# tally.net
KiCad netlist of a schematic drawn in EAGLE
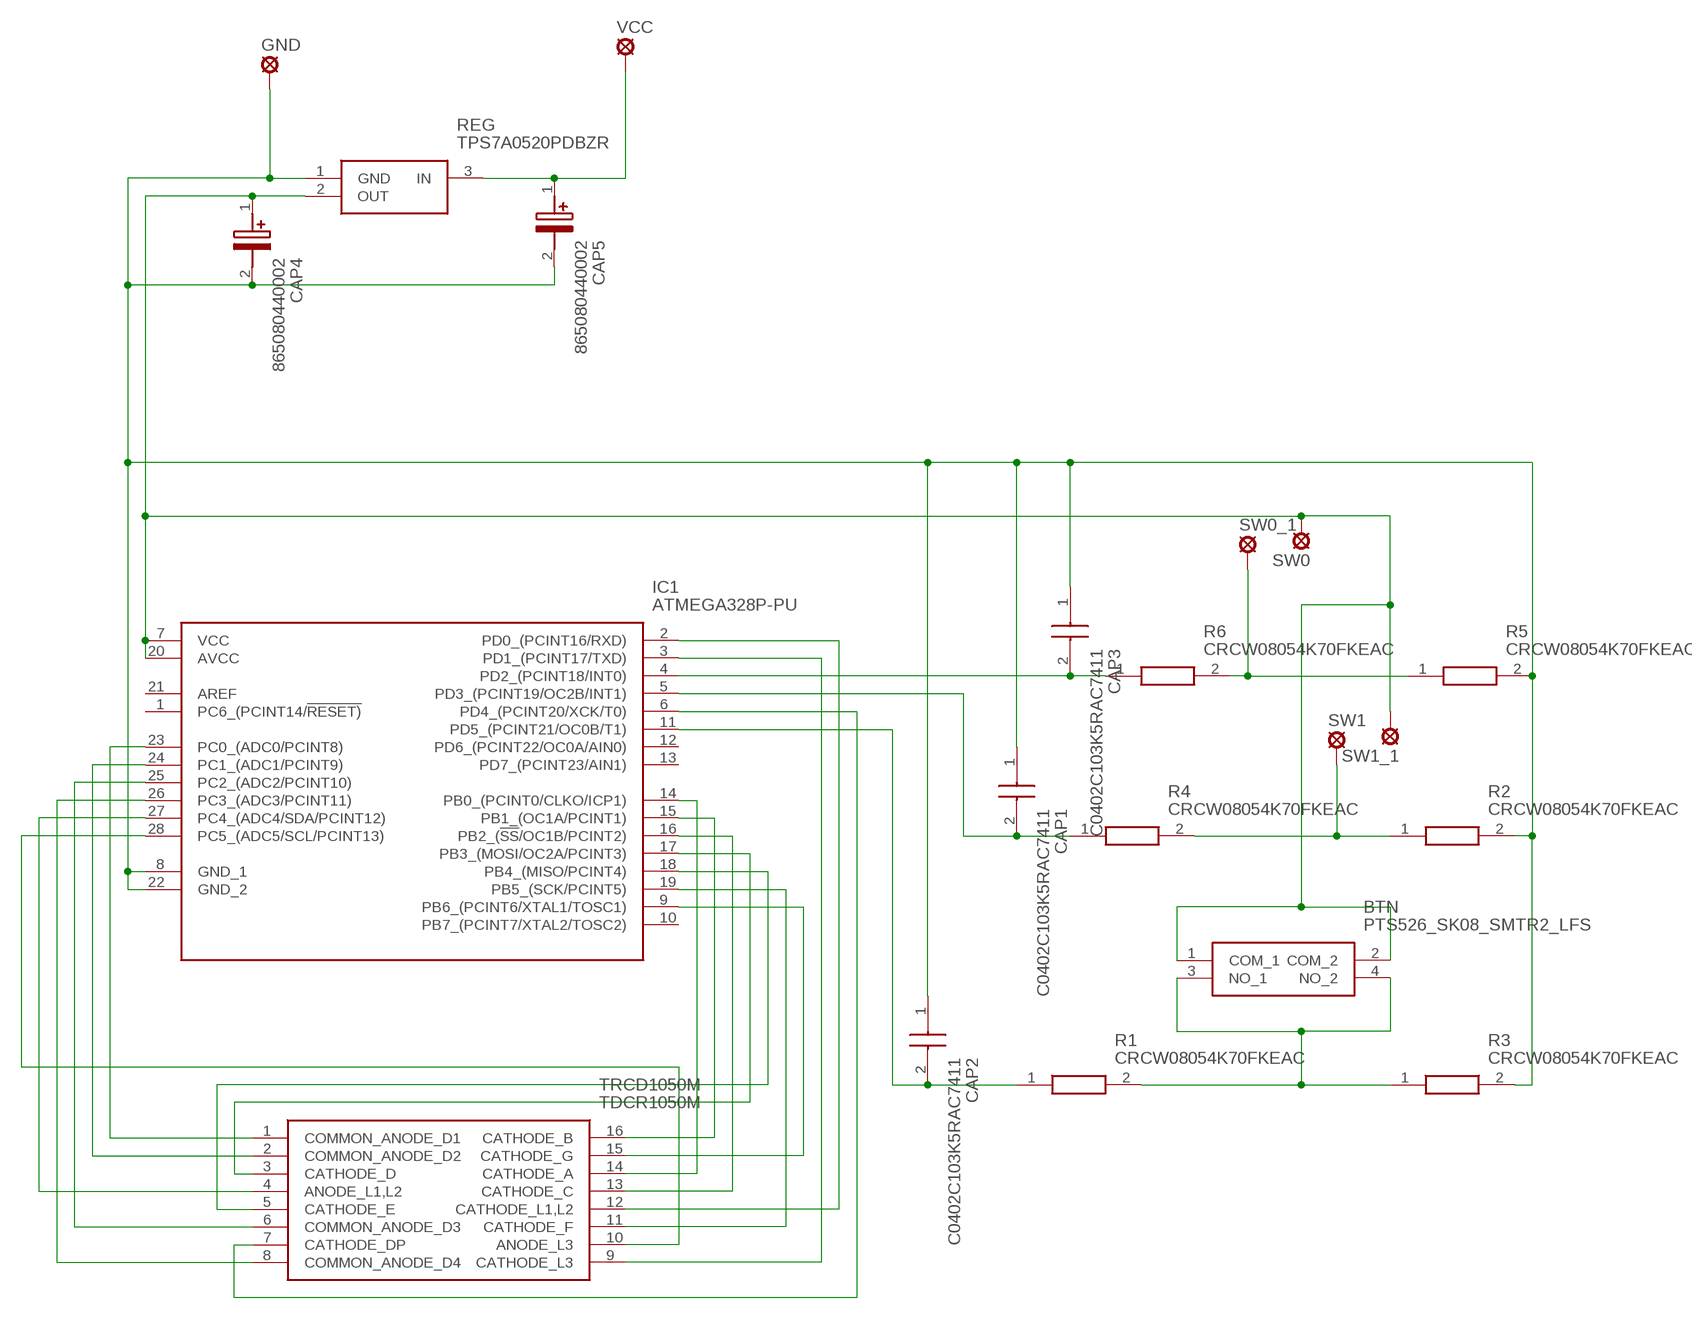
[diagram p0: schematic, sheet 1]

(export (version "E")
  (design (tool "Eeschema 10.0.6"))
  (components
    (comp (ref "BTN")
      (value "PTS526_SK08_SMTR2_LFS")
      (footprint "eagle-import:PTS526SKG15SMTR2LFS")
      (fields
        (field (name "MANUFACTURER_PART_NUMBER") "PTS526 SK08 SMTR2 LFS")
        (field (name "MOUSER_PART_NUMBER") "611-PTS526SK08SMTR2L")
      )
      (libsource (lib "eagle-import") (part "PTS526_SK08_SMTR2_LFS"))
    )
    (comp (ref "CAP1")
      (value "C0402C103K5RAC7411")
      (footprint "eagle-import:CAPC1005X55N")
      (fields (field (name "MOUSER_PART_NUMBER") "80-C0402C103K5R7411"))
      (libsource (lib "eagle-import") (part "C0402C103K5RAC7411"))
    )
    (comp (ref "CAP2")
      (value "C0402C103K5RAC7411")
      (footprint "eagle-import:CAPC1005X55N")
      (fields (field (name "MOUSER_PART_NUMBER") "80-C0402C103K5R7411"))
      (libsource (lib "eagle-import") (part "C0402C103K5RAC7411"))
    )
    (comp (ref "CAP3")
      (value "C0402C103K5RAC7411")
      (footprint "eagle-import:CAPC1005X55N")
      (fields (field (name "MOUSER_PART_NUMBER") "80-C0402C103K5R7411"))
      (libsource (lib "eagle-import") (part "C0402C103K5RAC7411"))
    )
    (comp (ref "CAP4")
      (value "865080440002")
      (footprint "eagle-import:CAPAE400X550N")
      (fields (field (name "MOUSER_PART_NUMBER") "710-865080440002"))
      (libsource (lib "eagle-import") (part "865080440002"))
    )
    (comp (ref "CAP5")
      (value "865080440002")
      (footprint "eagle-import:CAPAE400X550N")
      (fields (field (name "MOUSER_PART_NUMBER") "710-865080440002"))
      (libsource (lib "eagle-import") (part "865080440002"))
    )
    (comp (ref "GND")
      (value "LSP11")
      (footprint "eagle-import:LSP11")
      (libsource (lib "eagle-import") (part "LSP11"))
    )
    (comp (ref "IC1")
      (value "ATMEGA328P-PU")
      (footprint "eagle-import:DIP794W53P254L3467H457Q28N")
      (fields (field (name "MOUSER_PART_NUMBER") "556-ATMEGA328P-PU"))
      (libsource (lib "eagle-import") (part "ATMEGA328P-PU"))
    )
    (comp (ref "R1")
      (value "CRCW08054K70FKEAC")
      (footprint "eagle-import:RESC2012X60N")
      (fields (field (name "MOUSER_PART_NUMBER") "71-CRCW08054K70FKEAC"))
      (libsource (lib "eagle-import") (part "CRCW08054K70FKEAC"))
    )
    (comp (ref "R2")
      (value "CRCW08054K70FKEAC")
      (footprint "eagle-import:RESC2012X60N")
      (fields (field (name "MOUSER_PART_NUMBER") "71-CRCW08054K70FKEAC"))
      (libsource (lib "eagle-import") (part "CRCW08054K70FKEAC"))
    )
    (comp (ref "R3")
      (value "CRCW08054K70FKEAC")
      (footprint "eagle-import:RESC2012X60N")
      (fields (field (name "MOUSER_PART_NUMBER") "71-CRCW08054K70FKEAC"))
      (libsource (lib "eagle-import") (part "CRCW08054K70FKEAC"))
    )
    (comp (ref "R4")
      (value "CRCW08054K70FKEAC")
      (footprint "eagle-import:RESC2012X60N")
      (fields (field (name "MOUSER_PART_NUMBER") "71-CRCW08054K70FKEAC"))
      (libsource (lib "eagle-import") (part "CRCW08054K70FKEAC"))
    )
    (comp (ref "R5")
      (value "CRCW08054K70FKEAC")
      (footprint "eagle-import:RESC2012X60N")
      (fields (field (name "MOUSER_PART_NUMBER") "71-CRCW08054K70FKEAC"))
      (libsource (lib "eagle-import") (part "CRCW08054K70FKEAC"))
    )
    (comp (ref "R6")
      (value "CRCW08054K70FKEAC")
      (footprint "eagle-import:RESC2012X60N")
      (fields (field (name "MOUSER_PART_NUMBER") "71-CRCW08054K70FKEAC"))
      (libsource (lib "eagle-import") (part "CRCW08054K70FKEAC"))
    )
    (comp (ref "REG")
      (value "TPS7A0520PDBZR")
      (footprint "eagle-import:SOT95P237X112-3N")
      (fields (field (name "MOUSER_PART_NUMBER") "595-TPS7A0520PDBZR"))
      (libsource (lib "eagle-import") (part "TPS7A0520PDBZR"))
    )
    (comp (ref "SW0")
      (value "LSP11")
      (footprint "eagle-import:LSP11")
      (libsource (lib "eagle-import") (part "LSP11"))
    )
    (comp (ref "SW0_1")
      (value "LSP11")
      (footprint "eagle-import:LSP11")
      (libsource (lib "eagle-import") (part "LSP11"))
    )
    (comp (ref "SW1")
      (value "LSP11")
      (footprint "eagle-import:LSP11")
      (libsource (lib "eagle-import") (part "LSP11"))
    )
    (comp (ref "SW1_1")
      (value "LSP11")
      (footprint "eagle-import:LSP11")
      (libsource (lib "eagle-import") (part "LSP11"))
    )
    (comp (ref "TRCD1050M")
      (value "TDCR1050M")
      (footprint "eagle-import:DIPS1016W50P254L4020H725Q16N")
      (fields (field (name "MOUSER_PART_NUMBER") "78-TDCR1050M"))
      (libsource (lib "eagle-import") (part "TDCR1050M"))
    )
    (comp (ref "VCC")
      (value "LSP11")
      (footprint "eagle-import:LSP11")
      (libsource (lib "eagle-import") (part "LSP11"))
    )
  )
  (nets
    (net (code "1") (name "Net-(BTN-COM_1)") (class "Default")
      (node (ref "BTN") (pin "1") (pinfunction "COM_1_1") (pintype "bidirectional"))
      (node (ref "BTN") (pin "2") (pinfunction "COM_2_2") (pintype "bidirectional"))
      (node (ref "CAP4") (pin "1") (pinfunction "+_1") (pintype "bidirectional"))
      (node (ref "IC1") (pin "20") (pinfunction "AVCC_20") (pintype "bidirectional"))
      (node (ref "IC1") (pin "7") (pinfunction "VCC_7") (pintype "bidirectional"))
      (node (ref "REG") (pin "2") (pinfunction "OUT_2") (pintype "bidirectional"))
      (node (ref "SW0") (pin "MP") (pinfunction "MP_MP") (pintype "passive"))
      (node (ref "SW1_1") (pin "MP") (pinfunction "MP_MP") (pintype "passive"))
    )
    (net (code "2") (name "Net-(BTN-NO_1)") (class "Default")
      (node (ref "BTN") (pin "3") (pinfunction "NO_1_3") (pintype "bidirectional"))
      (node (ref "BTN") (pin "4") (pinfunction "NO_2_4") (pintype "bidirectional"))
      (node (ref "R1") (pin "2") (pinfunction "2_2") (pintype "bidirectional"))
      (node (ref "R3") (pin "1") (pinfunction "1_1") (pintype "bidirectional"))
    )
    (net (code "3") (name "Net-(CAP4--)") (class "Default")
      (node (ref "CAP1") (pin "1") (pinfunction "1_1") (pintype "bidirectional"))
      (node (ref "CAP2") (pin "1") (pinfunction "1_1") (pintype "bidirectional"))
      (node (ref "CAP3") (pin "1") (pinfunction "1_1") (pintype "bidirectional"))
      (node (ref "CAP4") (pin "2") (pinfunction "-_2") (pintype "bidirectional"))
      (node (ref "CAP5") (pin "2") (pinfunction "-_2") (pintype "bidirectional"))
      (node (ref "GND") (pin "MP") (pinfunction "MP_MP") (pintype "passive"))
      (node (ref "IC1") (pin "22") (pinfunction "GND_2_22") (pintype "bidirectional"))
      (node (ref "IC1") (pin "8") (pinfunction "GND_1_8") (pintype "bidirectional"))
      (node (ref "R2") (pin "2") (pinfunction "2_2") (pintype "bidirectional"))
      (node (ref "R3") (pin "2") (pinfunction "2_2") (pintype "bidirectional"))
      (node (ref "R5") (pin "2") (pinfunction "2_2") (pintype "bidirectional"))
      (node (ref "REG") (pin "1") (pinfunction "GND_1") (pintype "bidirectional"))
    )
    (net (code "4") (name "Net-(CAP5-+)") (class "Default")
      (node (ref "CAP5") (pin "1") (pinfunction "+_1") (pintype "bidirectional"))
      (node (ref "REG") (pin "3") (pinfunction "IN_3") (pintype "bidirectional"))
      (node (ref "VCC") (pin "MP") (pinfunction "MP_MP") (pintype "passive"))
    )
    (net (code "5") (name "Net-(IC1-PB0_(PCINT0{slash}CLKO{slash}ICP1))") (class "Default")
      (node (ref "IC1") (pin "14") (pinfunction "PB0_(PCINT0/CLKO/ICP1)_14") (pintype "bidirectional"))
      (node (ref "TRCD1050M") (pin "14") (pinfunction "CATHODE_A_14") (pintype "bidirectional"))
    )
    (net (code "6") (name "Net-(IC1-PB1_(OC1A{slash}PCINT1))") (class "Default")
      (node (ref "IC1") (pin "15") (pinfunction "PB1_(OC1A/PCINT1)_15") (pintype "bidirectional"))
      (node (ref "TRCD1050M") (pin "16") (pinfunction "CATHODE_B_16") (pintype "bidirectional"))
    )
    (net (code "7") (name "Net-(IC1-PB2_(~{SS}{slash}OC1B{slash}PCINT2))") (class "Default")
      (node (ref "IC1") (pin "16") (pinfunction "PB2_(~{SS}/OC1B/PCINT2)_16") (pintype "bidirectional"))
      (node (ref "TRCD1050M") (pin "13") (pinfunction "CATHODE_C_13") (pintype "bidirectional"))
    )
    (net (code "8") (name "Net-(IC1-PB3_(MOSI{slash}OC2A{slash}PCINT3))") (class "Default")
      (node (ref "IC1") (pin "17") (pinfunction "PB3_(MOSI/OC2A/PCINT3)_17") (pintype "bidirectional"))
      (node (ref "TRCD1050M") (pin "3") (pinfunction "CATHODE_D_3") (pintype "bidirectional"))
    )
    (net (code "9") (name "Net-(IC1-PB4_(MISO{slash}PCINT4))") (class "Default")
      (node (ref "IC1") (pin "18") (pinfunction "PB4_(MISO/PCINT4)_18") (pintype "bidirectional"))
      (node (ref "TRCD1050M") (pin "5") (pinfunction "CATHODE_E_5") (pintype "bidirectional"))
    )
    (net (code "10") (name "Net-(IC1-PB5_(SCK{slash}PCINT5))") (class "Default")
      (node (ref "IC1") (pin "19") (pinfunction "PB5_(SCK/PCINT5)_19") (pintype "bidirectional"))
      (node (ref "TRCD1050M") (pin "11") (pinfunction "CATHODE_F_11") (pintype "bidirectional"))
    )
    (net (code "11") (name "Net-(IC1-PB6_(PCINT6{slash}XTAL1{slash}TOSC1))") (class "Default")
      (node (ref "IC1") (pin "9") (pinfunction "PB6_(PCINT6/XTAL1/TOSC1)_9") (pintype "bidirectional"))
      (node (ref "TRCD1050M") (pin "15") (pinfunction "CATHODE_G_15") (pintype "bidirectional"))
    )
    (net (code "12") (name "Net-(IC1-PC0_(ADC0{slash}PCINT8))") (class "Default")
      (node (ref "IC1") (pin "23") (pinfunction "PC0_(ADC0/PCINT8)_23") (pintype "bidirectional"))
      (node (ref "TRCD1050M") (pin "1") (pinfunction "COMMON_ANODE_D1_1") (pintype "bidirectional"))
    )
    (net (code "13") (name "Net-(IC1-PC1_(ADC1{slash}PCINT9))") (class "Default")
      (node (ref "IC1") (pin "24") (pinfunction "PC1_(ADC1/PCINT9)_24") (pintype "bidirectional"))
      (node (ref "TRCD1050M") (pin "2") (pinfunction "COMMON_ANODE_D2_2") (pintype "bidirectional"))
    )
    (net (code "14") (name "Net-(IC1-PC2_(ADC2{slash}PCINT10))") (class "Default")
      (node (ref "IC1") (pin "25") (pinfunction "PC2_(ADC2/PCINT10)_25") (pintype "bidirectional"))
      (node (ref "TRCD1050M") (pin "6") (pinfunction "COMMON_ANODE_D3_6") (pintype "bidirectional"))
    )
    (net (code "15") (name "Net-(IC1-PC3_(ADC3{slash}PCINT11))") (class "Default")
      (node (ref "IC1") (pin "26") (pinfunction "PC3_(ADC3/PCINT11)_26") (pintype "bidirectional"))
      (node (ref "TRCD1050M") (pin "8") (pinfunction "COMMON_ANODE_D4_8") (pintype "bidirectional"))
    )
    (net (code "16") (name "Net-(IC1-PC4_(ADC4{slash}SDA{slash}PCINT12))") (class "Default")
      (node (ref "IC1") (pin "27") (pinfunction "PC4_(ADC4/SDA/PCINT12)_27") (pintype "bidirectional"))
      (node (ref "TRCD1050M") (pin "4") (pinfunction "ANODE_L1,L2_4") (pintype "bidirectional"))
    )
    (net (code "17") (name "Net-(IC1-PC5_(ADC5{slash}SCL{slash}PCINT13))") (class "Default")
      (node (ref "IC1") (pin "28") (pinfunction "PC5_(ADC5/SCL/PCINT13)_28") (pintype "bidirectional"))
      (node (ref "TRCD1050M") (pin "10") (pinfunction "ANODE_L3_10") (pintype "bidirectional"))
    )
    (net (code "18") (name "Net-(IC1-PD0_(PCINT16{slash}RXD))") (class "Default")
      (node (ref "IC1") (pin "2") (pinfunction "PD0_(PCINT16/RXD)_2") (pintype "bidirectional"))
      (node (ref "TRCD1050M") (pin "12") (pinfunction "CATHODE_L1,L2_12") (pintype "bidirectional"))
    )
    (net (code "19") (name "Net-(IC1-PD1_(PCINT17{slash}TXD))") (class "Default")
      (node (ref "IC1") (pin "3") (pinfunction "PD1_(PCINT17/TXD)_3") (pintype "bidirectional"))
      (node (ref "TRCD1050M") (pin "9") (pinfunction "CATHODE_L3_9") (pintype "bidirectional"))
    )
    (net (code "20") (name "Net-(IC1-PD2_(PCINT18{slash}INT0))") (class "Default")
      (node (ref "CAP3") (pin "2") (pinfunction "2_2") (pintype "bidirectional"))
      (node (ref "IC1") (pin "4") (pinfunction "PD2_(PCINT18/INT0)_4") (pintype "bidirectional"))
      (node (ref "R6") (pin "1") (pinfunction "1_1") (pintype "bidirectional"))
    )
    (net (code "21") (name "Net-(IC1-PD3_(PCINT19{slash}OC2B{slash}INT1))") (class "Default")
      (node (ref "CAP1") (pin "2") (pinfunction "2_2") (pintype "bidirectional"))
      (node (ref "IC1") (pin "5") (pinfunction "PD3_(PCINT19/OC2B/INT1)_5") (pintype "bidirectional"))
      (node (ref "R4") (pin "1") (pinfunction "1_1") (pintype "bidirectional"))
    )
    (net (code "22") (name "Net-(IC1-PD4_(PCINT20{slash}XCK{slash}T0))") (class "Default")
      (node (ref "IC1") (pin "6") (pinfunction "PD4_(PCINT20/XCK/T0)_6") (pintype "bidirectional"))
      (node (ref "TRCD1050M") (pin "7") (pinfunction "CATHODE_DP_7") (pintype "bidirectional"))
    )
    (net (code "23") (name "Net-(IC1-PD5_(PCINT21{slash}OC0B{slash}T1))") (class "Default")
      (node (ref "CAP2") (pin "2") (pinfunction "2_2") (pintype "bidirectional"))
      (node (ref "IC1") (pin "11") (pinfunction "PD5_(PCINT21/OC0B/T1)_11") (pintype "bidirectional"))
      (node (ref "R1") (pin "1") (pinfunction "1_1") (pintype "bidirectional"))
    )
    (net (code "24") (name "Net-(R2-Pad1)") (class "Default")
      (node (ref "R2") (pin "1") (pinfunction "1_1") (pintype "bidirectional"))
      (node (ref "R4") (pin "2") (pinfunction "2_2") (pintype "bidirectional"))
      (node (ref "SW1") (pin "MP") (pinfunction "MP_MP") (pintype "passive"))
    )
    (net (code "25") (name "Net-(R5-Pad1)") (class "Default")
      (node (ref "R5") (pin "1") (pinfunction "1_1") (pintype "bidirectional"))
      (node (ref "R6") (pin "2") (pinfunction "2_2") (pintype "bidirectional"))
      (node (ref "SW0_1") (pin "MP") (pinfunction "MP_MP") (pintype "passive"))
    )
    (net (code "26") (name "unconnected-(IC1-AREF-Pad21)") (class "Default")
      (node (ref "IC1") (pin "21") (pinfunction "AREF_21") (pintype "bidirectional"))
    )
    (net (code "27") (name "unconnected-(IC1-PB7_(PCINT7{slash}XTAL2{slash}TOSC2)-Pad10)") (class "Default")
      (node (ref "IC1") (pin "10") (pinfunction "PB7_(PCINT7/XTAL2/TOSC2)_10") (pintype "bidirectional"))
    )
    (net (code "28") (name "unconnected-(IC1-PC6_(PCINT14{slash}~{RESET})-Pad1)") (class "Default")
      (node (ref "IC1") (pin "1") (pinfunction "PC6_(PCINT14/~{RESET})_1") (pintype "bidirectional"))
    )
    (net (code "29") (name "unconnected-(IC1-PD6_(PCINT22{slash}OC0A{slash}AIN0)-Pad12)") (class "Default")
      (node (ref "IC1") (pin "12") (pinfunction "PD6_(PCINT22/OC0A/AIN0)_12") (pintype "bidirectional"))
    )
    (net (code "30") (name "unconnected-(IC1-PD7_(PCINT23{slash}AIN1)-Pad13)") (class "Default")
      (node (ref "IC1") (pin "13") (pinfunction "PD7_(PCINT23/AIN1)_13") (pintype "bidirectional"))
    )
  )
)
